# Trinket_M0_rev_D.net
KiCad netlist of a schematic drawn in EAGLE
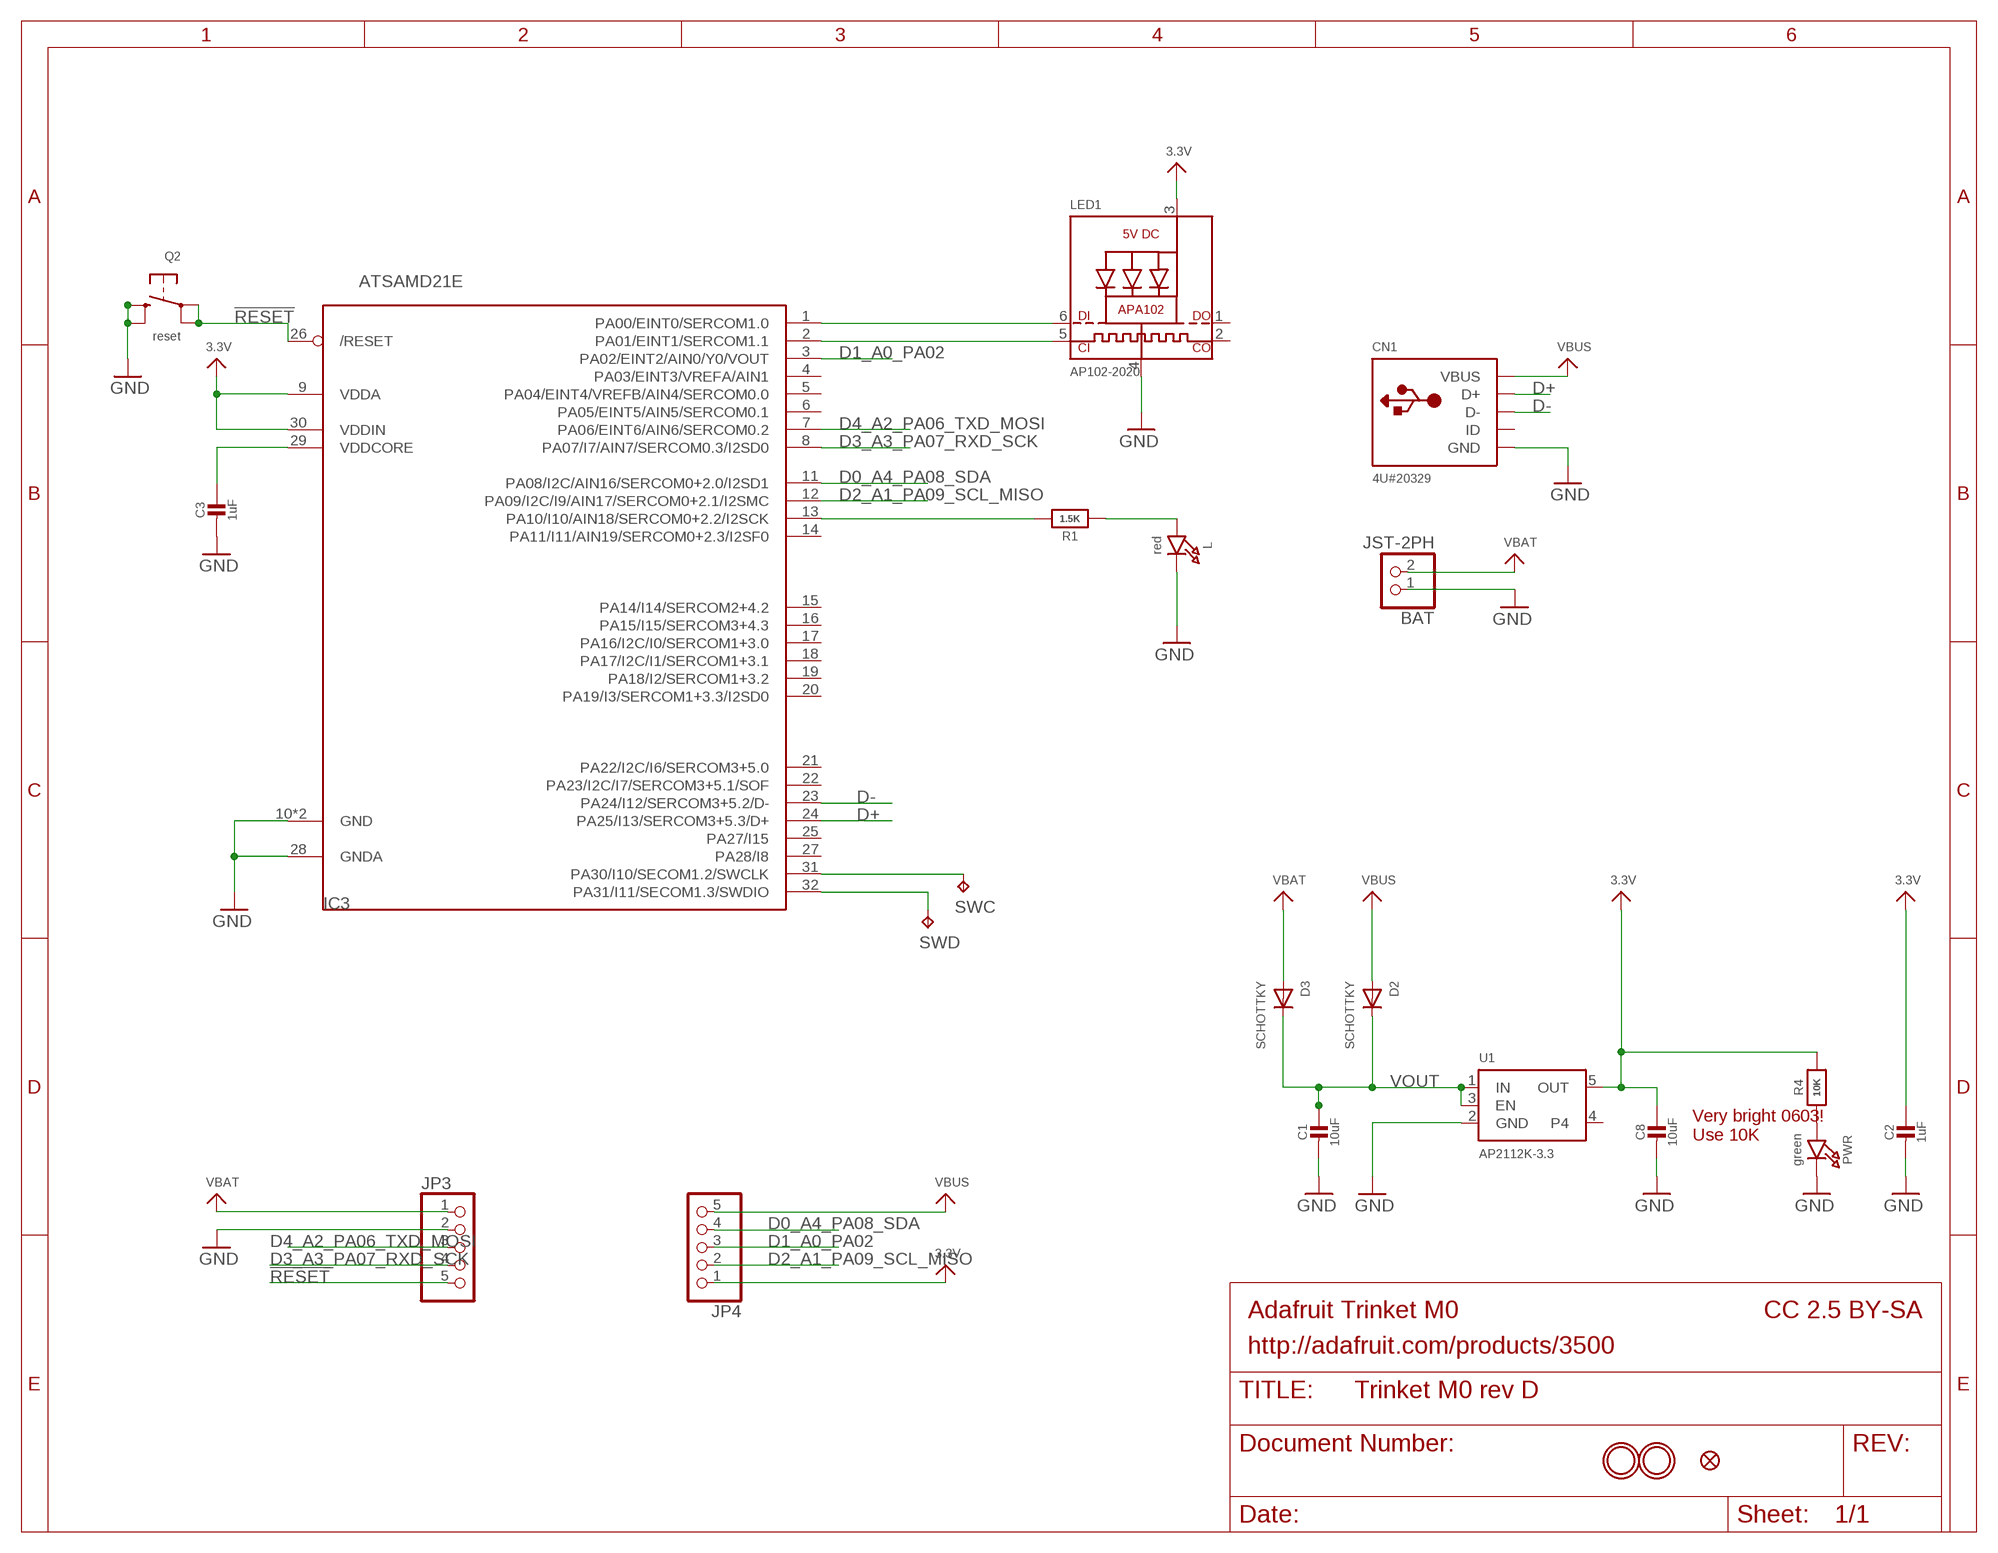
[diagram p0: schematic, sheet 1]

(export (version "E")
  (design (tool "Eeschema 10.0.6"))
  (components
    (comp (ref "BAT")
      (value "JST-2PH")
      (footprint "eagle-import:JSTPH2")
      (libsource (lib "eagle-import") (part "CON_JST_PH_2PIN"))
    )
    (comp (ref "C1")
      (value "10uF")
      (footprint "eagle-import:0805-NO")
      (libsource (lib "eagle-import") (part "CAP_CERAMIC0805-NOOUTLINE"))
    )
    (comp (ref "C2")
      (value "1uF")
      (footprint "eagle-import:0603-NO")
      (libsource (lib "eagle-import") (part "CAP_CERAMIC0603_NO"))
    )
    (comp (ref "C3")
      (value "1uF")
      (footprint "eagle-import:0603-NO")
      (libsource (lib "eagle-import") (part "CAP_CERAMIC0603_NO"))
    )
    (comp (ref "C8")
      (value "10uF")
      (footprint "eagle-import:0805-NO")
      (libsource (lib "eagle-import") (part "CAP_CERAMIC0805-NOOUTLINE"))
    )
    (comp (ref "CN1")
      (value "4U#20329")
      (footprint "eagle-import:4UCONN_20329_V2")
      (libsource (lib "eagle-import") (part "USB_MICRO_20329_V2"))
    )
    (comp (ref "D2")
      (value "SCHOTTKY")
      (footprint "eagle-import:SOD-123FL")
      (libsource (lib "eagle-import") (part "DIODE_SOD-123FL"))
    )
    (comp (ref "D3")
      (value "SCHOTTKY")
      (footprint "eagle-import:SOD-123FL")
      (libsource (lib "eagle-import") (part "DIODE_SOD-123FL"))
    )
    (comp (ref "IC3")
      (value "ATSAMD21E")
      (footprint "eagle-import:QFN32_5MM")
      (libsource (lib "eagle-import") (part "ATSAMD21E"))
    )
    (comp (ref "JP3")
      (value "HEADER-1X576MIL")
      (footprint "eagle-import:1X05_ROUND_76")
      (libsource (lib "eagle-import") (part "HEADER-1X576MIL"))
    )
    (comp (ref "JP4")
      (value "HEADER-1X576MIL")
      (footprint "eagle-import:1X05_ROUND_76")
      (libsource (lib "eagle-import") (part "HEADER-1X576MIL"))
    )
    (comp (ref "L")
      (value "red")
      (footprint "eagle-import:CHIPLED_0603_NOOUTLINE")
      (libsource (lib "eagle-import") (part "LED0603_NOOUTLINE"))
    )
    (comp (ref "LED1")
      (value "AP102-2020")
      (footprint "eagle-import:APA102_2020")
      (libsource (lib "eagle-import") (part "APA1022020"))
    )
    (comp (ref "PWR")
      (value "green")
      (footprint "eagle-import:CHIPLED_0603_NOOUTLINE")
      (libsource (lib "eagle-import") (part "LED0603_NOOUTLINE"))
    )
    (comp (ref "Q2")
      (value "reset")
      (footprint "eagle-import:BTN_KMR2_4.6X2.8")
      (libsource (lib "eagle-import") (part "SWITCH_TACT_SMT4.6X2.8"))
    )
    (comp (ref "R1")
      (value "1.5K")
      (footprint "eagle-import:0603-NO")
      (libsource (lib "eagle-import") (part "RESISTOR_0603_NOOUT"))
    )
    (comp (ref "R4")
      (value "10K")
      (footprint "eagle-import:0603-NO")
      (libsource (lib "eagle-import") (part "RESISTOR_0603_NOOUT"))
    )
    (comp (ref "SWC")
      (value "TPB1,27")
      (footprint "eagle-import:B1,27")
      (libsource (lib "eagle-import") (part "TPB1,27"))
    )
    (comp (ref "SWD")
      (value "TPB1,27")
      (footprint "eagle-import:B1,27")
      (libsource (lib "eagle-import") (part "TPB1,27"))
    )
    (comp (ref "U$6")
      (value "FIDUCIAL_1MM")
      (footprint "eagle-import:FIDUCIAL_1MM")
      (libsource (lib "eagle-import") (part "FIDUCIAL_1MM"))
    )
    (comp (ref "U$8")
      (value "MOUNTINGHOLE2.0")
      (footprint "eagle-import:MOUNTINGHOLE_2.0_PLATED")
      (libsource (lib "eagle-import") (part "MOUNTINGHOLE2.0"))
    )
    (comp (ref "U$9")
      (value "MOUNTINGHOLE2.0")
      (footprint "eagle-import:MOUNTINGHOLE_2.0_PLATED")
      (libsource (lib "eagle-import") (part "MOUNTINGHOLE2.0"))
    )
    (comp (ref "U1")
      (value "AP2112K-3.3")
      (footprint "eagle-import:SOT23-5")
      (libsource (lib "eagle-import") (part "VREG_SOT23-5"))
    )
  )
  (nets
    (net (code "1") (name "/D+") (class "Default")
      (node (ref "CN1") (pin "D+") (pinfunction "D+_D+") (pintype "bidirectional"))
      (node (ref "IC3") (pin "24") (pinfunction "PA25/I13/SERCOM3+5.3/D+_24") (pintype "bidirectional"))
    )
    (net (code "2") (name "/D-") (class "Default")
      (node (ref "CN1") (pin "D-") (pinfunction "D-_D-") (pintype "bidirectional"))
      (node (ref "IC3") (pin "23") (pinfunction "PA24/I12/SERCOM3+5.2/D-_23") (pintype "bidirectional"))
    )
    (net (code "3") (name "/D0_A4_PA08_SDA") (class "Default")
      (node (ref "IC3") (pin "11") (pinfunction "PA08/I2C/AIN16/SERCOM0+2.0/I2SD1_11") (pintype "bidirectional"))
      (node (ref "JP4") (pin "4") (pinfunction "4_4") (pintype "passive"))
    )
    (net (code "4") (name "/D1_A0_PA02") (class "Default")
      (node (ref "IC3") (pin "3") (pinfunction "PA02/EINT2/AIN0/Y0/VOUT_3") (pintype "bidirectional"))
      (node (ref "JP4") (pin "3") (pinfunction "3_3") (pintype "passive"))
    )
    (net (code "5") (name "/D2_A1_PA09_SCL_MISO") (class "Default")
      (node (ref "IC3") (pin "12") (pinfunction "PA09/I2C/I9/AIN17/SERCOM0+2.1/I2SMC_12") (pintype "bidirectional"))
      (node (ref "JP4") (pin "2") (pinfunction "2_2") (pintype "passive"))
    )
    (net (code "6") (name "/D3_A3_PA07_RXD_SCK") (class "Default")
      (node (ref "IC3") (pin "8") (pinfunction "PA07/I7/AIN7/SERCOM0.3/I2SD0_8") (pintype "bidirectional"))
      (node (ref "JP3") (pin "4") (pinfunction "4_4") (pintype "passive"))
    )
    (net (code "7") (name "/D4_A2_PA06_TXD_MOSI") (class "Default")
      (node (ref "IC3") (pin "7") (pinfunction "PA06/EINT6/AIN6/SERCOM0.2_7") (pintype "bidirectional"))
      (node (ref "JP3") (pin "3") (pinfunction "3_3") (pintype "passive"))
    )
    (net (code "8") (name "/VOUT") (class "Default")
      (node (ref "C1") (pin "1") (pinfunction "1_1") (pintype "passive"))
      (node (ref "D2") (pin "C") (pinfunction "C_C") (pintype "passive"))
      (node (ref "D3") (pin "C") (pinfunction "C_C") (pintype "passive"))
      (node (ref "U1") (pin "1") (pinfunction "IN_1") (pintype "power_in"))
      (node (ref "U1") (pin "3") (pinfunction "EN_3") (pintype "input"))
    )
    (net (code "9") (name "/~{RESET}") (class "Default")
      (node (ref "IC3") (pin "26") (pinfunction "/RESET_26") (pintype "bidirectional"))
      (node (ref "JP3") (pin "5") (pinfunction "5_5") (pintype "passive"))
      (node (ref "Q2") (pin "A") (pinfunction "P_A") (pintype "passive"))
      (node (ref "Q2") (pin "A'") (pinfunction "P1_A'") (pintype "passive"))
    )
    (net (code "10") (name "3.3V") (class "Default")
      (node (ref "C2") (pin "1") (pinfunction "1_1") (pintype "passive"))
      (node (ref "C8") (pin "1") (pinfunction "1_1") (pintype "passive"))
      (node (ref "IC3") (pin "30") (pinfunction "VDDIN_30") (pintype "power_in"))
      (node (ref "IC3") (pin "9") (pinfunction "VDDA_9") (pintype "power_in"))
      (node (ref "JP4") (pin "1") (pinfunction "1_1") (pintype "passive"))
      (node (ref "LED1") (pin "3") (pinfunction "VDD_3") (pintype "power_in"))
      (node (ref "R4") (pin "2") (pinfunction "2_2") (pintype "passive"))
      (node (ref "U1") (pin "5") (pinfunction "OUT_5") (pintype "power_in"))
    )
    (net (code "11") (name "GND") (class "Default")
      (node (ref "BAT") (pin "1") (pinfunction "1_1") (pintype "passive"))
      (node (ref "C1") (pin "2") (pinfunction "2_2") (pintype "passive"))
      (node (ref "C2") (pin "2") (pinfunction "2_2") (pintype "passive"))
      (node (ref "C3") (pin "2") (pinfunction "2_2") (pintype "passive"))
      (node (ref "C8") (pin "2") (pinfunction "2_2") (pintype "passive"))
      (node (ref "CN1") (pin "BASE@1") (pinfunction "GND_BASE@1") (pintype "power_in"))
      (node (ref "CN1") (pin "BASE@2") (pinfunction "GND_BASE@2") (pintype "power_in"))
      (node (ref "CN1") (pin "GND") (pinfunction "GND_GND") (pintype "power_in"))
      (node (ref "CN1") (pin "SPRT@1") (pinfunction "GND_SPRT@1") (pintype "power_in"))
      (node (ref "CN1") (pin "SPRT@2") (pinfunction "GND_SPRT@2") (pintype "power_in"))
      (node (ref "CN1") (pin "SPRT@3") (pinfunction "GND_SPRT@3") (pintype "power_in"))
      (node (ref "CN1") (pin "SPRT@4") (pinfunction "GND_SPRT@4") (pintype "power_in"))
      (node (ref "IC3") (pin "10") (pinfunction "GND_10") (pintype "power_in"))
      (node (ref "IC3") (pin "28") (pinfunction "GNDA_28") (pintype "power_in"))
      (node (ref "IC3") (pin "33") (pinfunction "GND_33") (pintype "power_in"))
      (node (ref "JP3") (pin "2") (pinfunction "2_2") (pintype "passive"))
      (node (ref "L") (pin "C") (pinfunction "C_C") (pintype "passive"))
      (node (ref "LED1") (pin "4") (pinfunction "GND_4") (pintype "power_in"))
      (node (ref "PWR") (pin "C") (pinfunction "C_C") (pintype "passive"))
      (node (ref "Q2") (pin "B") (pinfunction "S_B") (pintype "passive"))
      (node (ref "Q2") (pin "B'") (pinfunction "S1_B'") (pintype "passive"))
      (node (ref "U1") (pin "2") (pinfunction "GND_2") (pintype "power_in"))
    )
    (net (code "12") (name "Net-(IC3-PA00{slash}EINT0{slash}SERCOM1.0)") (class "Default")
      (node (ref "IC3") (pin "1") (pinfunction "PA00/EINT0/SERCOM1.0_1") (pintype "bidirectional"))
      (node (ref "LED1") (pin "6") (pinfunction "DI_6") (pintype "input"))
    )
    (net (code "13") (name "Net-(IC3-PA01{slash}EINT1{slash}SERCOM1.1)") (class "Default")
      (node (ref "IC3") (pin "2") (pinfunction "PA01/EINT1/SERCOM1.1_2") (pintype "bidirectional"))
      (node (ref "LED1") (pin "5") (pinfunction "CKI_5") (pintype "input"))
    )
    (net (code "14") (name "Net-(IC3-PA10{slash}I10{slash}AIN18{slash}SERCOM0+2.2{slash}I2SCK)") (class "Default")
      (node (ref "IC3") (pin "13") (pinfunction "PA10/I10/AIN18/SERCOM0+2.2/I2SCK_13") (pintype "bidirectional"))
      (node (ref "R1") (pin "2") (pinfunction "2_2") (pintype "passive"))
    )
    (net (code "15") (name "Net-(IC3-PA30{slash}I10{slash}SECOM1.2{slash}SWCLK)") (class "Default")
      (node (ref "IC3") (pin "31") (pinfunction "PA30/I10/SECOM1.2/SWCLK_31") (pintype "bidirectional"))
      (node (ref "SWC") (pin "TP") (pinfunction "TP_TP") (pintype "input"))
    )
    (net (code "16") (name "Net-(IC3-PA31{slash}I11{slash}SECOM1.3{slash}SWDIO)") (class "Default")
      (node (ref "IC3") (pin "32") (pinfunction "PA31/I11/SECOM1.3/SWDIO_32") (pintype "bidirectional"))
      (node (ref "SWD") (pin "TP") (pinfunction "TP_TP") (pintype "input"))
    )
    (net (code "17") (name "Net-(IC3-VDDCORE)") (class "Default")
      (node (ref "C3") (pin "1") (pinfunction "1_1") (pintype "passive"))
      (node (ref "IC3") (pin "29") (pinfunction "VDDCORE_29") (pintype "power_in"))
    )
    (net (code "18") (name "Net-(L-PadA)") (class "Default")
      (node (ref "L") (pin "A") (pinfunction "A_A") (pintype "passive"))
      (node (ref "R1") (pin "1") (pinfunction "1_1") (pintype "passive"))
    )
    (net (code "19") (name "Net-(PWR-PadA)") (class "Default")
      (node (ref "PWR") (pin "A") (pinfunction "A_A") (pintype "passive"))
      (node (ref "R4") (pin "1") (pinfunction "1_1") (pintype "passive"))
    )
    (net (code "20") (name "VBAT") (class "Default")
      (node (ref "BAT") (pin "2") (pinfunction "2_2") (pintype "passive"))
      (node (ref "D3") (pin "A") (pinfunction "A_A") (pintype "passive"))
      (node (ref "JP3") (pin "1") (pinfunction "1_1") (pintype "passive"))
    )
    (net (code "21") (name "VBUS") (class "Default")
      (node (ref "CN1") (pin "VBUS") (pinfunction "VBUS_VBUS") (pintype "power_in"))
      (node (ref "D2") (pin "A") (pinfunction "A_A") (pintype "passive"))
      (node (ref "JP4") (pin "5") (pinfunction "5_5") (pintype "passive"))
    )
    (net (code "22") (name "unconnected-(CN1-PadID)") (class "Default")
      (node (ref "CN1") (pin "ID") (pinfunction "ID_ID") (pintype "bidirectional"))
    )
    (net (code "23") (name "unconnected-(IC3-PA03{slash}EINT3{slash}VREFA{slash}AIN1-Pad4)") (class "Default")
      (node (ref "IC3") (pin "4") (pinfunction "PA03/EINT3/VREFA/AIN1_4") (pintype "bidirectional"))
    )
    (net (code "24") (name "unconnected-(IC3-PA04{slash}EINT4{slash}VREFB{slash}AIN4{slash}SERCOM0.0-Pad5)") (class "Default")
      (node (ref "IC3") (pin "5") (pinfunction "PA04/EINT4/VREFB/AIN4/SERCOM0.0_5") (pintype "bidirectional"))
    )
    (net (code "25") (name "unconnected-(IC3-PA05{slash}EINT5{slash}AIN5{slash}SERCOM0.1-Pad6)") (class "Default")
      (node (ref "IC3") (pin "6") (pinfunction "PA05/EINT5/AIN5/SERCOM0.1_6") (pintype "bidirectional"))
    )
    (net (code "26") (name "unconnected-(IC3-PA11{slash}I11{slash}AIN19{slash}SERCOM0+2.3{slash}I2SF0-Pad14)") (class "Default")
      (node (ref "IC3") (pin "14") (pinfunction "PA11/I11/AIN19/SERCOM0+2.3/I2SF0_14") (pintype "bidirectional"))
    )
    (net (code "27") (name "unconnected-(IC3-PA14{slash}I14{slash}SERCOM2+4.2-Pad15)") (class "Default")
      (node (ref "IC3") (pin "15") (pinfunction "PA14/I14/SERCOM2+4.2_15") (pintype "bidirectional"))
    )
    (net (code "28") (name "unconnected-(IC3-PA15{slash}I15{slash}SERCOM3+4.3-Pad16)") (class "Default")
      (node (ref "IC3") (pin "16") (pinfunction "PA15/I15/SERCOM3+4.3_16") (pintype "bidirectional"))
    )
    (net (code "29") (name "unconnected-(IC3-PA16{slash}I2C{slash}I0{slash}SERCOM1+3.0-Pad17)") (class "Default")
      (node (ref "IC3") (pin "17") (pinfunction "PA16/I2C/I0/SERCOM1+3.0_17") (pintype "bidirectional"))
    )
    (net (code "30") (name "unconnected-(IC3-PA17{slash}I2C{slash}I1{slash}SERCOM1+3.1-Pad18)") (class "Default")
      (node (ref "IC3") (pin "18") (pinfunction "PA17/I2C/I1/SERCOM1+3.1_18") (pintype "bidirectional"))
    )
    (net (code "31") (name "unconnected-(IC3-PA18{slash}I2{slash}SERCOM1+3.2-Pad19)") (class "Default")
      (node (ref "IC3") (pin "19") (pinfunction "PA18/I2/SERCOM1+3.2_19") (pintype "bidirectional"))
    )
    (net (code "32") (name "unconnected-(IC3-PA19{slash}I3{slash}SERCOM1+3.3{slash}I2SD0-Pad20)") (class "Default")
      (node (ref "IC3") (pin "20") (pinfunction "PA19/I3/SERCOM1+3.3/I2SD0_20") (pintype "bidirectional"))
    )
    (net (code "33") (name "unconnected-(IC3-PA22{slash}I2C{slash}I6{slash}SERCOM3+5.0-Pad21)") (class "Default")
      (node (ref "IC3") (pin "21") (pinfunction "PA22/I2C/I6/SERCOM3+5.0_21") (pintype "bidirectional"))
    )
    (net (code "34") (name "unconnected-(IC3-PA23{slash}I2C{slash}I7{slash}SERCOM3+5.1{slash}SOF-Pad22)") (class "Default")
      (node (ref "IC3") (pin "22") (pinfunction "PA23/I2C/I7/SERCOM3+5.1/SOF_22") (pintype "bidirectional"))
    )
    (net (code "35") (name "unconnected-(IC3-PA27{slash}I15-Pad25)") (class "Default")
      (node (ref "IC3") (pin "25") (pinfunction "PA27/I15_25") (pintype "bidirectional"))
    )
    (net (code "36") (name "unconnected-(IC3-PA28{slash}I8-Pad27)") (class "Default")
      (node (ref "IC3") (pin "27") (pinfunction "PA28/I8_27") (pintype "bidirectional"))
    )
    (net (code "37") (name "unconnected-(LED1-CKO-Pad2)") (class "Default")
      (node (ref "LED1") (pin "2") (pinfunction "CKO_2") (pintype "output"))
    )
    (net (code "38") (name "unconnected-(LED1-DO-Pad1)") (class "Default")
      (node (ref "LED1") (pin "1") (pinfunction "DO_1") (pintype "output"))
    )
    (net (code "39") (name "unconnected-(U1-P4-Pad4)") (class "Default")
      (node (ref "U1") (pin "4") (pinfunction "P4_4") (pintype "bidirectional"))
    )
  )
)
